# FPGA_PWR.net
KiCad netlist of a schematic drawn in Altium Designer
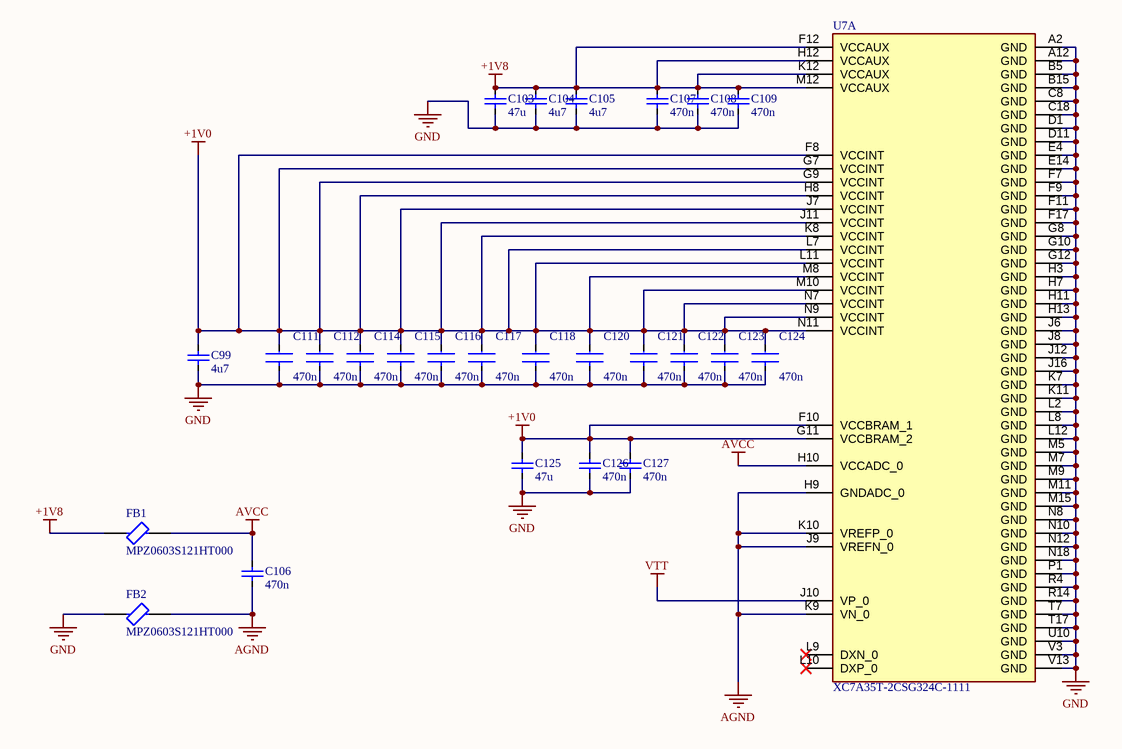
[diagram p0: FPGA PWR.SchDoc]

(export (version "E")
  (design (tool "Eeschema 10.0.6"))
  (components
    (comp (ref "C99")
      (value "4u7")
      (footprint "FP-C1005-050-0_20-0_10-IPC_C")
      (description "4.7UF 10V X5R 0402")
      (fields (field (name "TOLERANCE") "10%") (field (name "PART NUMBER") "C1005X5R1A475K050BE"))
      (libsource (lib "Schlib1") (part "C1005X5R1A475K050BE"))
    )
    (comp (ref "C103")
      (value "47u")
      (footprint "FP-C2012-125-0_2-IPC_C")
      (description "MLCC 47μF ±20% 10V X5R SMD 0805 Multilayer Ceramic Capacitors")
      (fields (field (name "VOLTAGE") "10V") (field (name "TOLERANCE") "20%"))
      (libsource (lib "Schlib1") (part "C2012X5R1A476M125AC"))
    )
    (comp (ref "C104")
      (value "4u7")
      (footprint "FP-C1005-050-0_20-0_10-IPC_C")
      (description "MLCC  4.7UF ±20 10V X5R 0402")
      (fields (field (name "TOLERANCE") "10%") (field (name "PART NUMBER") "C1005X5R1A475K050BE"))
      (libsource (lib "Schlib1") (part "C1005X5R1A475K050BE"))
    )
    (comp (ref "C105")
      (value "4u7")
      (footprint "FP-C1005-050-0_20-0_10-IPC_C")
      (description "MLCC  4.7UF ±20 10V X5R 0402")
      (fields (field (name "TOLERANCE") "10%") (field (name "PART NUMBER") "C1005X5R1A475K050BE"))
      (libsource (lib "Schlib1") (part "C1005X5R1A475K050BE"))
    )
    (comp (ref "C106")
      (value "470n")
      (footprint "pcblib1:FP-C1005-050-0_05-IPC_C")
      (description "MLCC 470nF ±10% 25V X5R SMD 0402")
      (fields (field (name "VOLTAGE") "25V") (field (name "TOLERANCE") "10%"))
      (libsource (lib "Schlib1") (part "C1005X5R1E474K050BB"))
    )
    (comp (ref "C107")
      (value "470n")
      (footprint "pcblib1:FP-C1005-050-0_05-IPC_C")
      (description "MLCC 470nF ±10% 25V X5R SMD 0402")
      (fields (field (name "VOLTAGE") "25V") (field (name "TOLERANCE") "10%"))
      (libsource (lib "Schlib1") (part "C1005X5R1E474K050BB"))
    )
    (comp (ref "C108")
      (value "470n")
      (footprint "pcblib1:FP-C1005-050-0_05-IPC_C")
      (description "MLCC 470nF ±10% 25V X5R SMD 0402")
      (fields (field (name "VOLTAGE") "25V") (field (name "TOLERANCE") "10%"))
      (libsource (lib "Schlib1") (part "C1005X5R1E474K050BB"))
    )
    (comp (ref "C109")
      (value "470n")
      (footprint "pcblib1:FP-C1005-050-0_05-IPC_C")
      (description "MLCC 470nF ±10% 25V X5R SMD 0402")
      (fields (field (name "VOLTAGE") "25V") (field (name "TOLERANCE") "10%"))
      (libsource (lib "Schlib1") (part "C1005X5R1E474K050BB"))
    )
    (comp (ref "C111")
      (value "470n")
      (footprint "FP-C1005-050-0_05-IPC_C")
      (description "Multilayer Ceramic Capacitors 470nF ±10% 25V X5R SMD 0402")
      (fields (field (name "VOLTAGE") "25V") (field (name "TOLERANCE") "10%"))
      (libsource (lib "Schlib1") (part "b4654b650e69147ec39a6b967a45e02"))
    )
    (comp (ref "C112")
      (value "470n")
      (footprint "FP-C1005-050-0_05-IPC_C")
      (description "Multilayer Ceramic Capacitors 470nF ±10% 25V X5R SMD 0402")
      (fields (field (name "VOLTAGE") "25V") (field (name "TOLERANCE") "10%"))
      (libsource (lib "Schlib1") (part "b4654b650e69147ec39a6b967a45e02"))
    )
    (comp (ref "C114")
      (value "470n")
      (footprint "FP-C1005-050-0_05-IPC_C")
      (description "Multilayer Ceramic Capacitors 470nF ±10% 25V X5R SMD 0402")
      (fields (field (name "VOLTAGE") "25V") (field (name "TOLERANCE") "10%"))
      (libsource (lib "Schlib1") (part "b4654b650e69147ec39a6b967a45e02"))
    )
    (comp (ref "C115")
      (value "470n")
      (footprint "FP-C1005-050-0_05-IPC_C")
      (description "Multilayer Ceramic Capacitors 470nF ±10% 25V X5R SMD 0402")
      (fields (field (name "VOLTAGE") "25V") (field (name "TOLERANCE") "10%"))
      (libsource (lib "Schlib1") (part "b4654b650e69147ec39a6b967a45e02"))
    )
    (comp (ref "C116")
      (value "470n")
      (footprint "FP-C1005-050-0_05-IPC_C")
      (description "Multilayer Ceramic Capacitors 470nF ±10% 25V X5R SMD 0402")
      (fields (field (name "VOLTAGE") "25V") (field (name "TOLERANCE") "10%"))
      (libsource (lib "Schlib1") (part "b4654b650e69147ec39a6b967a45e02"))
    )
    (comp (ref "C117")
      (value "470n")
      (footprint "FP-C1005-050-0_05-IPC_C")
      (description "Multilayer Ceramic Capacitors 470nF ±10% 25V X5R SMD 0402")
      (fields (field (name "VOLTAGE") "25V") (field (name "TOLERANCE") "10%"))
      (libsource (lib "Schlib1") (part "b4654b650e69147ec39a6b967a45e02"))
    )
    (comp (ref "C118")
      (value "470n")
      (footprint "FP-C1005-050-0_05-IPC_C")
      (description "Multilayer Ceramic Capacitors 470nF ±10% 25V X5R SMD 0402")
      (fields (field (name "VOLTAGE") "25V") (field (name "TOLERANCE") "10%"))
      (libsource (lib "Schlib1") (part "b4654b650e69147ec39a6b967a45e02"))
    )
    (comp (ref "C120")
      (value "470n")
      (footprint "FP-C1005-050-0_05-IPC_C")
      (description "Multilayer Ceramic Capacitors 470nF ±10% 25V X5R SMD 0402")
      (fields (field (name "VOLTAGE") "25V") (field (name "TOLERANCE") "10%"))
      (libsource (lib "Schlib1") (part "b4654b650e69147ec39a6b967a45e02"))
    )
    (comp (ref "C121")
      (value "470n")
      (footprint "FP-C1005-050-0_05-IPC_C")
      (description "Multilayer Ceramic Capacitors 470nF ±10% 25V X5R SMD 0402")
      (fields (field (name "VOLTAGE") "25V") (field (name "TOLERANCE") "10%"))
      (libsource (lib "Schlib1") (part "b4654b650e69147ec39a6b967a45e02"))
    )
    (comp (ref "C122")
      (value "470n")
      (footprint "FP-C1005-050-0_05-IPC_C")
      (description "Multilayer Ceramic Capacitors 470nF ±10% 25V X5R SMD 0402")
      (fields (field (name "VOLTAGE") "25V") (field (name "TOLERANCE") "10%"))
      (libsource (lib "Schlib1") (part "b4654b650e69147ec39a6b967a45e02"))
    )
    (comp (ref "C123")
      (value "470n")
      (footprint "FP-C1005-050-0_05-IPC_C")
      (description "Multilayer Ceramic Capacitors 470nF ±10% 25V X5R SMD 0402")
      (fields (field (name "VOLTAGE") "25V") (field (name "TOLERANCE") "10%"))
      (libsource (lib "Schlib1") (part "b4654b650e69147ec39a6b967a45e02"))
    )
    (comp (ref "C124")
      (value "470n")
      (footprint "FP-C1005-050-0_05-IPC_C")
      (description "Multilayer Ceramic Capacitors 470nF ±10% 25V X5R SMD 0402")
      (fields (field (name "VOLTAGE") "25V") (field (name "TOLERANCE") "10%"))
      (libsource (lib "Schlib1") (part "b4654b650e69147ec39a6b967a45e02"))
    )
    (comp (ref "C125")
      (value "47u")
      (footprint "FP-C2012-125-0_2-IPC_C")
      (description "MLCC 47μF ±20% 10V X5R SMD 0805 Multilayer Ceramic Capacitors")
      (fields (field (name "VOLTAGE") "10V") (field (name "TOLERANCE") "20%"))
      (libsource (lib "Schlib1") (part "C2012X5R1A476M125AC"))
    )
    (comp (ref "C126")
      (value "470n")
      (footprint "pcblib1:FP-C1005-050-0_05-IPC_C")
      (description "MLCC 470nF ±10% 25V X5R SMD 0402")
      (fields (field (name "VOLTAGE") "25V") (field (name "TOLERANCE") "10%"))
      (libsource (lib "Schlib1") (part "C1005X5R1E474K050BB"))
    )
    (comp (ref "C127")
      (value "470n")
      (footprint "pcblib1:FP-C1005-050-0_05-IPC_C")
      (description "MLCC 470nF ±10% 25V X5R SMD 0402")
      (fields (field (name "VOLTAGE") "25V") (field (name "TOLERANCE") "10%"))
      (libsource (lib "Schlib1") (part "C1005X5R1E474K050BB"))
    )
    (comp (ref "FB1")
      (value "MPZ0603S121HT000")
      (footprint "FP-MPZ0603-IPC_C")
      (description "CHIP BEADS FOR GENERAL SIGNAL LI")
      (libsource (lib "Schlib1") (part "MPZ0603S121HT000"))
    )
    (comp (ref "FB2")
      (value "MPZ0603S121HT000")
      (footprint "FP-MPZ0603-IPC_C")
      (description "CHIP BEADS FOR GENERAL SIGNAL LI")
      (libsource (lib "Schlib1") (part "MPZ0603S121HT000"))
    )
    (comp (ref "U7")
      (value "XC7A35T-2CSG324C-1111")
      (footprint "PCBLIB1:BGA324C80P18X18_1500X1500X150")
      (description "Integrated Circuit")
      (fields
        (field (name "MANUFACTURER_PART_NUMBER") "XC7A35T-2CSG324C")
        (field (name "MOUSER PART NUMBER") "217-XC7A35T-2CSG324C")
      )
      (libsource (lib "Schlib1") (part "XC7A35T-2CSG324C-1111"))
    )
  )
  (nets
    (net (code "1") (name "+1V0") (class "Default")
      (node (ref "C111") (pin "2") (pinfunction "2_2") (pintype "passive"))
      (node (ref "C112") (pin "2") (pinfunction "2_2") (pintype "passive"))
      (node (ref "C114") (pin "2") (pinfunction "2_2") (pintype "passive"))
      (node (ref "C115") (pin "2") (pinfunction "2_2") (pintype "passive"))
      (node (ref "C116") (pin "2") (pinfunction "2_2") (pintype "passive"))
      (node (ref "C117") (pin "2") (pinfunction "2_2") (pintype "passive"))
      (node (ref "C118") (pin "2") (pinfunction "2_2") (pintype "passive"))
      (node (ref "C120") (pin "2") (pinfunction "2_2") (pintype "passive"))
      (node (ref "C121") (pin "2") (pinfunction "2_2") (pintype "passive"))
      (node (ref "C122") (pin "2") (pinfunction "2_2") (pintype "passive"))
      (node (ref "C123") (pin "2") (pinfunction "2_2") (pintype "passive"))
      (node (ref "C124") (pin "2") (pinfunction "2_2") (pintype "passive"))
      (node (ref "C125") (pin "1") (pinfunction "1_1") (pintype "passive"))
      (node (ref "C126") (pin "1") (pinfunction "1_1") (pintype "passive"))
      (node (ref "C127") (pin "1") (pinfunction "1_1") (pintype "passive"))
      (node (ref "C99") (pin "1") (pinfunction "1_1") (pintype "passive"))
      (node (ref "U7") (pin "F10") (pinfunction "VCCBRAM_1_F10") (pintype "passive"))
      (node (ref "U7") (pin "F8") (pinfunction "VCCINT_F8") (pintype "passive"))
      (node (ref "U7") (pin "G11") (pinfunction "VCCBRAM_2_G11") (pintype "passive"))
      (node (ref "U7") (pin "G7") (pinfunction "VCCINT_G7") (pintype "passive"))
      (node (ref "U7") (pin "G9") (pinfunction "VCCINT_G9") (pintype "passive"))
      (node (ref "U7") (pin "H8") (pinfunction "VCCINT_H8") (pintype "passive"))
      (node (ref "U7") (pin "J11") (pinfunction "VCCINT_J11") (pintype "passive"))
      (node (ref "U7") (pin "J7") (pinfunction "VCCINT_J7") (pintype "passive"))
      (node (ref "U7") (pin "K8") (pinfunction "VCCINT_K8") (pintype "passive"))
      (node (ref "U7") (pin "L11") (pinfunction "VCCINT_L11") (pintype "passive"))
      (node (ref "U7") (pin "L7") (pinfunction "VCCINT_L7") (pintype "passive"))
      (node (ref "U7") (pin "M10") (pinfunction "VCCINT_M10") (pintype "passive"))
      (node (ref "U7") (pin "M8") (pinfunction "VCCINT_M8") (pintype "passive"))
      (node (ref "U7") (pin "N11") (pinfunction "VCCINT_N11") (pintype "passive"))
      (node (ref "U7") (pin "N7") (pinfunction "VCCINT_N7") (pintype "passive"))
      (node (ref "U7") (pin "N9") (pinfunction "VCCINT_N9") (pintype "passive"))
    )
    (net (code "2") (name "+1V8") (class "Default")
      (node (ref "C103") (pin "1") (pinfunction "1_1") (pintype "passive"))
      (node (ref "C104") (pin "1") (pinfunction "1_1") (pintype "passive"))
      (node (ref "C105") (pin "1") (pinfunction "1_1") (pintype "passive"))
      (node (ref "C107") (pin "1") (pinfunction "1_1") (pintype "passive"))
      (node (ref "C108") (pin "1") (pinfunction "1_1") (pintype "passive"))
      (node (ref "C109") (pin "1") (pinfunction "1_1") (pintype "passive"))
      (node (ref "FB1") (pin "1") (pinfunction "1_1") (pintype "passive"))
      (node (ref "U7") (pin "F12") (pinfunction "VCCAUX_F12") (pintype "passive"))
      (node (ref "U7") (pin "H12") (pinfunction "VCCAUX_H12") (pintype "passive"))
      (node (ref "U7") (pin "K12") (pinfunction "VCCAUX_K12") (pintype "passive"))
      (node (ref "U7") (pin "M12") (pinfunction "VCCAUX_M12") (pintype "passive"))
    )
    (net (code "3") (name "AGND") (class "Default")
      (node (ref "C106") (pin "2") (pinfunction "2_2") (pintype "passive"))
      (node (ref "FB2") (pin "2") (pinfunction "2_2") (pintype "passive"))
      (node (ref "U7") (pin "H9") (pinfunction "GNDADC_0_H9") (pintype "passive"))
      (node (ref "U7") (pin "J9") (pinfunction "VREFN_0_J9") (pintype "passive"))
      (node (ref "U7") (pin "K10") (pinfunction "VREFP_0_K10") (pintype "passive"))
      (node (ref "U7") (pin "K9") (pinfunction "VN_0_K9") (pintype "passive"))
    )
    (net (code "4") (name "AVCC") (class "Default")
      (node (ref "C106") (pin "1") (pinfunction "1_1") (pintype "passive"))
      (node (ref "FB1") (pin "2") (pinfunction "2_2") (pintype "passive"))
      (node (ref "U7") (pin "H10") (pinfunction "VCCADC_0_H10") (pintype "passive"))
    )
    (net (code "5") (name "GND") (class "Default")
      (node (ref "C103") (pin "2") (pinfunction "2_2") (pintype "passive"))
      (node (ref "C104") (pin "2") (pinfunction "2_2") (pintype "passive"))
      (node (ref "C105") (pin "2") (pinfunction "2_2") (pintype "passive"))
      (node (ref "C107") (pin "2") (pinfunction "2_2") (pintype "passive"))
      (node (ref "C108") (pin "2") (pinfunction "2_2") (pintype "passive"))
      (node (ref "C109") (pin "2") (pinfunction "2_2") (pintype "passive"))
      (node (ref "C111") (pin "1") (pinfunction "1_1") (pintype "passive"))
      (node (ref "C112") (pin "1") (pinfunction "1_1") (pintype "passive"))
      (node (ref "C114") (pin "1") (pinfunction "1_1") (pintype "passive"))
      (node (ref "C115") (pin "1") (pinfunction "1_1") (pintype "passive"))
      (node (ref "C116") (pin "1") (pinfunction "1_1") (pintype "passive"))
      (node (ref "C117") (pin "1") (pinfunction "1_1") (pintype "passive"))
      (node (ref "C118") (pin "1") (pinfunction "1_1") (pintype "passive"))
      (node (ref "C120") (pin "1") (pinfunction "1_1") (pintype "passive"))
      (node (ref "C121") (pin "1") (pinfunction "1_1") (pintype "passive"))
      (node (ref "C122") (pin "1") (pinfunction "1_1") (pintype "passive"))
      (node (ref "C123") (pin "1") (pinfunction "1_1") (pintype "passive"))
      (node (ref "C124") (pin "1") (pinfunction "1_1") (pintype "passive"))
      (node (ref "C125") (pin "2") (pinfunction "2_2") (pintype "passive"))
      (node (ref "C126") (pin "2") (pinfunction "2_2") (pintype "passive"))
      (node (ref "C127") (pin "2") (pinfunction "2_2") (pintype "passive"))
      (node (ref "C99") (pin "2") (pinfunction "2_2") (pintype "passive"))
      (node (ref "FB2") (pin "1") (pinfunction "1_1") (pintype "passive"))
      (node (ref "U7") (pin "A12") (pinfunction "GND_A12") (pintype "passive"))
      (node (ref "U7") (pin "A2") (pinfunction "GND_A2") (pintype "passive"))
      (node (ref "U7") (pin "B15") (pinfunction "GND_B15") (pintype "passive"))
      (node (ref "U7") (pin "B5") (pinfunction "GND_B5") (pintype "passive"))
      (node (ref "U7") (pin "C18") (pinfunction "GND_C18") (pintype "passive"))
      (node (ref "U7") (pin "C8") (pinfunction "GND_C8") (pintype "passive"))
      (node (ref "U7") (pin "D1") (pinfunction "GND_D1") (pintype "passive"))
      (node (ref "U7") (pin "D11") (pinfunction "GND_D11") (pintype "passive"))
      (node (ref "U7") (pin "E14") (pinfunction "GND_E14") (pintype "passive"))
      (node (ref "U7") (pin "E4") (pinfunction "GND_E4") (pintype "passive"))
      (node (ref "U7") (pin "F11") (pinfunction "GND_F11") (pintype "passive"))
      (node (ref "U7") (pin "F17") (pinfunction "GND_F17") (pintype "passive"))
      (node (ref "U7") (pin "F7") (pinfunction "GND_F7") (pintype "passive"))
      (node (ref "U7") (pin "F9") (pinfunction "GND_F9") (pintype "passive"))
      (node (ref "U7") (pin "G10") (pinfunction "GND_G10") (pintype "passive"))
      (node (ref "U7") (pin "G12") (pinfunction "GND_G12") (pintype "passive"))
      (node (ref "U7") (pin "G8") (pinfunction "GND_G8") (pintype "passive"))
      (node (ref "U7") (pin "H11") (pinfunction "GND_H11") (pintype "passive"))
      (node (ref "U7") (pin "H13") (pinfunction "GND_H13") (pintype "passive"))
      (node (ref "U7") (pin "H3") (pinfunction "GND_H3") (pintype "passive"))
      (node (ref "U7") (pin "H7") (pinfunction "GND_H7") (pintype "passive"))
      (node (ref "U7") (pin "J12") (pinfunction "GND_J12") (pintype "passive"))
      (node (ref "U7") (pin "J16") (pinfunction "GND_J16") (pintype "passive"))
      (node (ref "U7") (pin "J6") (pinfunction "GND_J6") (pintype "passive"))
      (node (ref "U7") (pin "J8") (pinfunction "GND_J8") (pintype "passive"))
      (node (ref "U7") (pin "K11") (pinfunction "GND_K11") (pintype "passive"))
      (node (ref "U7") (pin "K7") (pinfunction "GND_K7") (pintype "passive"))
      (node (ref "U7") (pin "L12") (pinfunction "GND_L12") (pintype "passive"))
      (node (ref "U7") (pin "L2") (pinfunction "GND_L2") (pintype "passive"))
      (node (ref "U7") (pin "L8") (pinfunction "GND_L8") (pintype "passive"))
      (node (ref "U7") (pin "M11") (pinfunction "GND_M11") (pintype "passive"))
      (node (ref "U7") (pin "M15") (pinfunction "GND_M15") (pintype "passive"))
      (node (ref "U7") (pin "M5") (pinfunction "GND_M5") (pintype "passive"))
      (node (ref "U7") (pin "M7") (pinfunction "GND_M7") (pintype "passive"))
      (node (ref "U7") (pin "M9") (pinfunction "GND_M9") (pintype "passive"))
      (node (ref "U7") (pin "N10") (pinfunction "GND_N10") (pintype "passive"))
      (node (ref "U7") (pin "N12") (pinfunction "GND_N12") (pintype "passive"))
      (node (ref "U7") (pin "N18") (pinfunction "GND_N18") (pintype "passive"))
      (node (ref "U7") (pin "N8") (pinfunction "GND_N8") (pintype "passive"))
      (node (ref "U7") (pin "P1") (pinfunction "GND_P1") (pintype "passive"))
      (node (ref "U7") (pin "R14") (pinfunction "GND_R14") (pintype "passive"))
      (node (ref "U7") (pin "R4") (pinfunction "GND_R4") (pintype "passive"))
      (node (ref "U7") (pin "T17") (pinfunction "GND_T17") (pintype "passive"))
      (node (ref "U7") (pin "T7") (pinfunction "GND_T7") (pintype "passive"))
      (node (ref "U7") (pin "U10") (pinfunction "GND_U10") (pintype "passive"))
      (node (ref "U7") (pin "V13") (pinfunction "GND_V13") (pintype "passive"))
      (node (ref "U7") (pin "V3") (pinfunction "GND_V3") (pintype "passive"))
    )
    (net (code "6") (name "VTT") (class "Default")
      (node (ref "U7") (pin "J10") (pinfunction "VP_0_J10") (pintype "passive"))
    )
    (net (code "7") (name "unconnected-(U7A-DXN_0-PadL9)") (class "Default")
      (node (ref "U7") (pin "L9") (pinfunction "DXN_0_L9") (pintype "passive+no_connect"))
    )
    (net (code "8") (name "unconnected-(U7A-DXP_0-PadL10)") (class "Default")
      (node (ref "U7") (pin "L10") (pinfunction "DXP_0_L10") (pintype "passive+no_connect"))
    )
  )
)
